# B133C.net
KiCad netlist of a schematic drawn in EAGLE
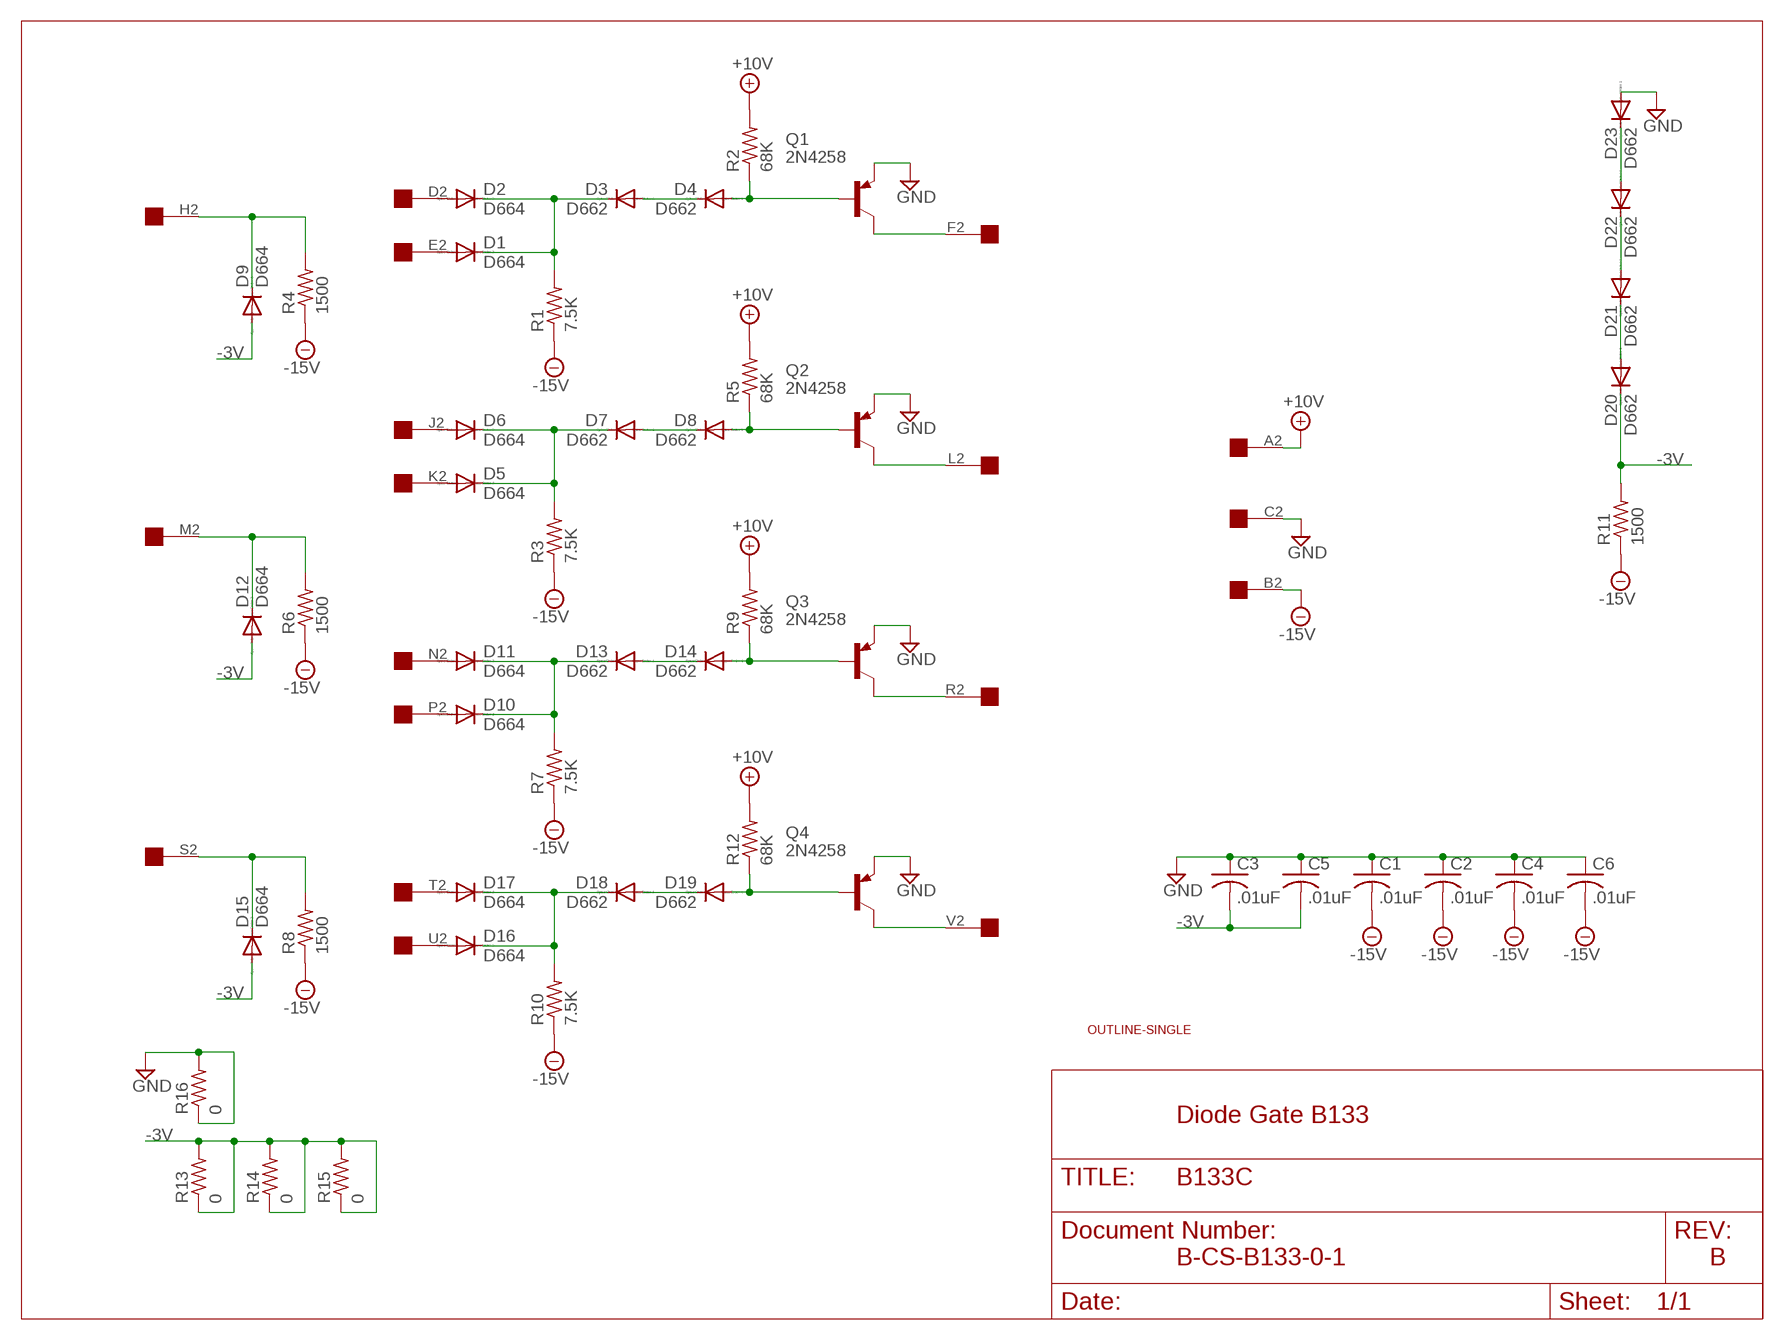
[diagram p0: schematic, sheet 1]

(export (version "E")
  (design (tool "Eeschema 10.0.6"))
  (components
    (comp (ref "C1")
      (value ".01uF")
      (footprint "eagle-import:C063-025X075")
      (libsource (lib "eagle-import") (part "C-US"))
    )
    (comp (ref "C2")
      (value ".01uF")
      (footprint "eagle-import:C063-025X075")
      (libsource (lib "eagle-import") (part "C-US"))
    )
    (comp (ref "C3")
      (value ".01uF")
      (footprint "eagle-import:C063-025X075")
      (libsource (lib "eagle-import") (part "C-US"))
    )
    (comp (ref "C4")
      (value ".01uF")
      (footprint "eagle-import:C063-025X075")
      (libsource (lib "eagle-import") (part "C-US"))
    )
    (comp (ref "C5")
      (value ".01uF")
      (footprint "eagle-import:C063-025X075")
      (libsource (lib "eagle-import") (part "C-US"))
    )
    (comp (ref "C6")
      (value ".01uF")
      (footprint "eagle-import:C063-025X075")
      (libsource (lib "eagle-import") (part "C-US"))
    )
    (comp (ref "D1")
      (value "D664")
      (footprint "eagle-import:DO35-10")
      (libsource (lib "eagle-import") (part "DIODE-DO35-10"))
    )
    (comp (ref "D2")
      (value "D664")
      (footprint "eagle-import:DO35-10")
      (libsource (lib "eagle-import") (part "DIODE-DO35-10"))
    )
    (comp (ref "D3")
      (value "D662")
      (footprint "eagle-import:DO35-10")
      (libsource (lib "eagle-import") (part "DIODE-DO35-10"))
    )
    (comp (ref "D4")
      (value "D662")
      (footprint "eagle-import:DO35-10")
      (libsource (lib "eagle-import") (part "DIODE-DO35-10"))
    )
    (comp (ref "D5")
      (value "D664")
      (footprint "eagle-import:DO35-10")
      (libsource (lib "eagle-import") (part "DIODE-DO35-10"))
    )
    (comp (ref "D6")
      (value "D664")
      (footprint "eagle-import:DO35-10")
      (libsource (lib "eagle-import") (part "DIODE-DO35-10"))
    )
    (comp (ref "D7")
      (value "D662")
      (footprint "eagle-import:DO35-10")
      (libsource (lib "eagle-import") (part "DIODE-DO35-10"))
    )
    (comp (ref "D8")
      (value "D662")
      (footprint "eagle-import:DO35-10")
      (libsource (lib "eagle-import") (part "DIODE-DO35-10"))
    )
    (comp (ref "D9")
      (value "D664")
      (footprint "eagle-import:DO35-10")
      (libsource (lib "eagle-import") (part "DIODE-DO35-10"))
    )
    (comp (ref "D10")
      (value "D664")
      (footprint "eagle-import:DO35-10")
      (libsource (lib "eagle-import") (part "DIODE-DO35-10"))
    )
    (comp (ref "D11")
      (value "D664")
      (footprint "eagle-import:DO35-10")
      (libsource (lib "eagle-import") (part "DIODE-DO35-10"))
    )
    (comp (ref "D12")
      (value "D664")
      (footprint "eagle-import:DO35-10")
      (libsource (lib "eagle-import") (part "DIODE-DO35-10"))
    )
    (comp (ref "D13")
      (value "D662")
      (footprint "eagle-import:DO35-10")
      (libsource (lib "eagle-import") (part "DIODE-DO35-10"))
    )
    (comp (ref "D14")
      (value "D662")
      (footprint "eagle-import:DO35-10")
      (libsource (lib "eagle-import") (part "DIODE-DO35-10"))
    )
    (comp (ref "D15")
      (value "D664")
      (footprint "eagle-import:DO35-10")
      (libsource (lib "eagle-import") (part "DIODE-DO35-10"))
    )
    (comp (ref "D16")
      (value "D664")
      (footprint "eagle-import:DO35-10")
      (libsource (lib "eagle-import") (part "DIODE-DO35-10"))
    )
    (comp (ref "D17")
      (value "D664")
      (footprint "eagle-import:DO35-10")
      (libsource (lib "eagle-import") (part "DIODE-DO35-10"))
    )
    (comp (ref "D18")
      (value "D662")
      (footprint "eagle-import:DO35-10")
      (libsource (lib "eagle-import") (part "DIODE-DO35-10"))
    )
    (comp (ref "D19")
      (value "D662")
      (footprint "eagle-import:DO35-10")
      (libsource (lib "eagle-import") (part "DIODE-DO35-10"))
    )
    (comp (ref "D20")
      (value "D662")
      (footprint "eagle-import:DO35-10")
      (libsource (lib "eagle-import") (part "DIODE-DO35-10"))
    )
    (comp (ref "D21")
      (value "D662")
      (footprint "eagle-import:DO35-10")
      (libsource (lib "eagle-import") (part "DIODE-DO35-10"))
    )
    (comp (ref "D22")
      (value "D662")
      (footprint "eagle-import:DO35-10")
      (libsource (lib "eagle-import") (part "DIODE-DO35-10"))
    )
    (comp (ref "D23")
      (value "D662")
      (footprint "eagle-import:DO35-10")
      (libsource (lib "eagle-import") (part "DIODE-DO35-10"))
    )
    (comp (ref "Q1")
      (value "2N4258")
      (footprint "eagle-import:TO5")
      (libsource (lib "eagle-import") (part "-PNP-TO5"))
    )
    (comp (ref "Q2")
      (value "2N4258")
      (footprint "eagle-import:TO5")
      (libsource (lib "eagle-import") (part "-PNP-TO5"))
    )
    (comp (ref "Q3")
      (value "2N4258")
      (footprint "eagle-import:TO5")
      (libsource (lib "eagle-import") (part "-PNP-TO5"))
    )
    (comp (ref "Q4")
      (value "2N4258")
      (footprint "eagle-import:TO5")
      (libsource (lib "eagle-import") (part "-PNP-TO5"))
    )
    (comp (ref "R1")
      (value "7.5K")
      (footprint "eagle-import:0207_10")
      (libsource (lib "eagle-import") (part "R-US_0207/10"))
    )
    (comp (ref "R2")
      (value "68K")
      (footprint "eagle-import:0207_10")
      (libsource (lib "eagle-import") (part "R-US_0207/10"))
    )
    (comp (ref "R3")
      (value "7.5K")
      (footprint "eagle-import:0207_10")
      (libsource (lib "eagle-import") (part "R-US_0207/10"))
    )
    (comp (ref "R4")
      (value "1500")
      (footprint "eagle-import:0207_10")
      (libsource (lib "eagle-import") (part "R-US_0207/10"))
    )
    (comp (ref "R5")
      (value "68K")
      (footprint "eagle-import:0207_10")
      (libsource (lib "eagle-import") (part "R-US_0207/10"))
    )
    (comp (ref "R6")
      (value "1500")
      (footprint "eagle-import:0207_10")
      (libsource (lib "eagle-import") (part "R-US_0207/10"))
    )
    (comp (ref "R7")
      (value "7.5K")
      (footprint "eagle-import:0207_10")
      (libsource (lib "eagle-import") (part "R-US_0207/10"))
    )
    (comp (ref "R8")
      (value "1500")
      (footprint "eagle-import:0207_10")
      (libsource (lib "eagle-import") (part "R-US_0207/10"))
    )
    (comp (ref "R9")
      (value "68K")
      (footprint "eagle-import:0207_10")
      (libsource (lib "eagle-import") (part "R-US_0207/10"))
    )
    (comp (ref "R10")
      (value "7.5K")
      (footprint "eagle-import:0207_10")
      (libsource (lib "eagle-import") (part "R-US_0207/10"))
    )
    (comp (ref "R11")
      (value "1500")
      (footprint "eagle-import:0207_10")
      (libsource (lib "eagle-import") (part "R-US_0207/10"))
    )
    (comp (ref "R12")
      (value "68K")
      (footprint "eagle-import:0207_10")
      (libsource (lib "eagle-import") (part "R-US_0207/10"))
    )
    (comp (ref "R13")
      (value "0")
      (footprint "eagle-import:0207_10")
      (libsource (lib "eagle-import") (part "R-US_0207/10"))
    )
    (comp (ref "R14")
      (value "0")
      (footprint "eagle-import:0207_10")
      (libsource (lib "eagle-import") (part "R-US_0207/10"))
    )
    (comp (ref "R15")
      (value "0")
      (footprint "eagle-import:0207_10")
      (libsource (lib "eagle-import") (part "R-US_0207/10"))
    )
    (comp (ref "R16")
      (value "0")
      (footprint "eagle-import:0207_10")
      (libsource (lib "eagle-import") (part "R-US_0207/10"))
    )
    (comp (ref "U$1")
      (value "OUTLINE-SINGLE")
      (footprint "eagle-import:SINGLE")
      (libsource (lib "eagle-import") (part "OUTLINE-SINGLE"))
    )
    (comp (ref "U$2")
      (value "EDGE-1")
      (footprint "eagle-import:EDGE-CON1")
      (libsource (lib "eagle-import") (part "EDGE-1"))
    )
  )
  (nets
    (net (code "1") (name "+10V") (class "Default")
      (node (ref "R12") (pin "2") (pinfunction "2_2") (pintype "passive"))
      (node (ref "R2") (pin "2") (pinfunction "2_2") (pintype "passive"))
      (node (ref "R5") (pin "2") (pinfunction "2_2") (pintype "passive"))
      (node (ref "R9") (pin "2") (pinfunction "2_2") (pintype "passive"))
      (node (ref "U$2") (pin "A2") (pinfunction "1_A2") (pintype "bidirectional"))
    )
    (net (code "2") (name "-15V") (class "Default")
      (node (ref "C1") (pin "2") (pinfunction "2_2") (pintype "passive"))
      (node (ref "C2") (pin "2") (pinfunction "2_2") (pintype "passive"))
      (node (ref "C4") (pin "2") (pinfunction "2_2") (pintype "passive"))
      (node (ref "C6") (pin "2") (pinfunction "2_2") (pintype "passive"))
      (node (ref "R1") (pin "1") (pinfunction "1_1") (pintype "passive"))
      (node (ref "R10") (pin "1") (pinfunction "1_1") (pintype "passive"))
      (node (ref "R11") (pin "1") (pinfunction "1_1") (pintype "passive"))
      (node (ref "R3") (pin "1") (pinfunction "1_1") (pintype "passive"))
      (node (ref "R4") (pin "1") (pinfunction "1_1") (pintype "passive"))
      (node (ref "R6") (pin "1") (pinfunction "1_1") (pintype "passive"))
      (node (ref "R7") (pin "1") (pinfunction "1_1") (pintype "passive"))
      (node (ref "R8") (pin "1") (pinfunction "1_1") (pintype "passive"))
      (node (ref "U$2") (pin "B2") (pinfunction "1_B2") (pintype "bidirectional"))
    )
    (net (code "3") (name "/-3V") (class "Default")
      (node (ref "C3") (pin "2") (pinfunction "2_2") (pintype "passive"))
      (node (ref "C5") (pin "2") (pinfunction "2_2") (pintype "passive"))
      (node (ref "D12") (pin "A") (pinfunction "A_A") (pintype "passive"))
      (node (ref "D15") (pin "A") (pinfunction "A_A") (pintype "passive"))
      (node (ref "D20") (pin "C") (pinfunction "C_C") (pintype "passive"))
      (node (ref "D9") (pin "A") (pinfunction "A_A") (pintype "passive"))
      (node (ref "R11") (pin "2") (pinfunction "2_2") (pintype "passive"))
      (node (ref "R13") (pin "1") (pinfunction "1_1") (pintype "passive"))
      (node (ref "R13") (pin "2") (pinfunction "2_2") (pintype "passive"))
      (node (ref "R14") (pin "1") (pinfunction "1_1") (pintype "passive"))
      (node (ref "R14") (pin "2") (pinfunction "2_2") (pintype "passive"))
      (node (ref "R15") (pin "1") (pinfunction "1_1") (pintype "passive"))
      (node (ref "R15") (pin "2") (pinfunction "2_2") (pintype "passive"))
    )
    (net (code "4") (name "GND") (class "Default")
      (node (ref "C1") (pin "1") (pinfunction "1_1") (pintype "passive"))
      (node (ref "C2") (pin "1") (pinfunction "1_1") (pintype "passive"))
      (node (ref "C3") (pin "1") (pinfunction "1_1") (pintype "passive"))
      (node (ref "C4") (pin "1") (pinfunction "1_1") (pintype "passive"))
      (node (ref "C5") (pin "1") (pinfunction "1_1") (pintype "passive"))
      (node (ref "C6") (pin "1") (pinfunction "1_1") (pintype "passive"))
      (node (ref "D23") (pin "A") (pinfunction "A_A") (pintype "passive"))
      (node (ref "Q1") (pin "1") (pinfunction "E_1") (pintype "passive"))
      (node (ref "Q2") (pin "1") (pinfunction "E_1") (pintype "passive"))
      (node (ref "Q3") (pin "1") (pinfunction "E_1") (pintype "passive"))
      (node (ref "Q4") (pin "1") (pinfunction "E_1") (pintype "passive"))
      (node (ref "R16") (pin "1") (pinfunction "1_1") (pintype "passive"))
      (node (ref "R16") (pin "2") (pinfunction "2_2") (pintype "passive"))
      (node (ref "U$2") (pin "C2") (pinfunction "1_C2") (pintype "bidirectional"))
    )
    (net (code "5") (name "Net-(D1-PadC)") (class "Default")
      (node (ref "D1") (pin "C") (pinfunction "C_C") (pintype "passive"))
      (node (ref "D2") (pin "C") (pinfunction "C_C") (pintype "passive"))
      (node (ref "D3") (pin "C") (pinfunction "C_C") (pintype "passive"))
      (node (ref "R1") (pin "2") (pinfunction "2_2") (pintype "passive"))
    )
    (net (code "6") (name "Net-(D3-PadA)") (class "Default")
      (node (ref "D3") (pin "A") (pinfunction "A_A") (pintype "passive"))
      (node (ref "D4") (pin "C") (pinfunction "C_C") (pintype "passive"))
    )
    (net (code "7") (name "Net-(D5-PadC)") (class "Default")
      (node (ref "D5") (pin "C") (pinfunction "C_C") (pintype "passive"))
      (node (ref "D6") (pin "C") (pinfunction "C_C") (pintype "passive"))
      (node (ref "D7") (pin "C") (pinfunction "C_C") (pintype "passive"))
      (node (ref "R3") (pin "2") (pinfunction "2_2") (pintype "passive"))
    )
    (net (code "8") (name "Net-(D7-PadA)") (class "Default")
      (node (ref "D7") (pin "A") (pinfunction "A_A") (pintype "passive"))
      (node (ref "D8") (pin "C") (pinfunction "C_C") (pintype "passive"))
    )
    (net (code "9") (name "Net-(D10-PadC)") (class "Default")
      (node (ref "D10") (pin "C") (pinfunction "C_C") (pintype "passive"))
      (node (ref "D11") (pin "C") (pinfunction "C_C") (pintype "passive"))
      (node (ref "D13") (pin "C") (pinfunction "C_C") (pintype "passive"))
      (node (ref "R7") (pin "2") (pinfunction "2_2") (pintype "passive"))
    )
    (net (code "10") (name "Net-(D13-PadA)") (class "Default")
      (node (ref "D13") (pin "A") (pinfunction "A_A") (pintype "passive"))
      (node (ref "D14") (pin "C") (pinfunction "C_C") (pintype "passive"))
    )
    (net (code "11") (name "Net-(D16-PadC)") (class "Default")
      (node (ref "D16") (pin "C") (pinfunction "C_C") (pintype "passive"))
      (node (ref "D17") (pin "C") (pinfunction "C_C") (pintype "passive"))
      (node (ref "D18") (pin "C") (pinfunction "C_C") (pintype "passive"))
      (node (ref "R10") (pin "2") (pinfunction "2_2") (pintype "passive"))
    )
    (net (code "12") (name "Net-(D18-PadA)") (class "Default")
      (node (ref "D18") (pin "A") (pinfunction "A_A") (pintype "passive"))
      (node (ref "D19") (pin "C") (pinfunction "C_C") (pintype "passive"))
    )
    (net (code "13") (name "Net-(D20-PadA)") (class "Default")
      (node (ref "D20") (pin "A") (pinfunction "A_A") (pintype "passive"))
      (node (ref "D21") (pin "C") (pinfunction "C_C") (pintype "passive"))
    )
    (net (code "14") (name "Net-(D21-PadA)") (class "Default")
      (node (ref "D21") (pin "A") (pinfunction "A_A") (pintype "passive"))
      (node (ref "D22") (pin "C") (pinfunction "C_C") (pintype "passive"))
    )
    (net (code "15") (name "Net-(D22-PadA)") (class "Default")
      (node (ref "D22") (pin "A") (pinfunction "A_A") (pintype "passive"))
      (node (ref "D23") (pin "C") (pinfunction "C_C") (pintype "passive"))
    )
    (net (code "16") (name "Net-(Q1-B)") (class "Default")
      (node (ref "D4") (pin "A") (pinfunction "A_A") (pintype "passive"))
      (node (ref "Q1") (pin "2") (pinfunction "B_2") (pintype "passive"))
      (node (ref "R2") (pin "1") (pinfunction "1_1") (pintype "passive"))
    )
    (net (code "17") (name "Net-(Q1-C)") (class "Default")
      (node (ref "Q1") (pin "3") (pinfunction "C_3") (pintype "passive"))
      (node (ref "U$2") (pin "F2") (pinfunction "1_F2") (pintype "bidirectional"))
    )
    (net (code "18") (name "Net-(Q2-B)") (class "Default")
      (node (ref "D8") (pin "A") (pinfunction "A_A") (pintype "passive"))
      (node (ref "Q2") (pin "2") (pinfunction "B_2") (pintype "passive"))
      (node (ref "R5") (pin "1") (pinfunction "1_1") (pintype "passive"))
    )
    (net (code "19") (name "Net-(Q2-C)") (class "Default")
      (node (ref "Q2") (pin "3") (pinfunction "C_3") (pintype "passive"))
      (node (ref "U$2") (pin "L2") (pinfunction "1_L2") (pintype "bidirectional"))
    )
    (net (code "20") (name "Net-(Q3-B)") (class "Default")
      (node (ref "D14") (pin "A") (pinfunction "A_A") (pintype "passive"))
      (node (ref "Q3") (pin "2") (pinfunction "B_2") (pintype "passive"))
      (node (ref "R9") (pin "1") (pinfunction "1_1") (pintype "passive"))
    )
    (net (code "21") (name "Net-(Q3-C)") (class "Default")
      (node (ref "Q3") (pin "3") (pinfunction "C_3") (pintype "passive"))
      (node (ref "U$2") (pin "R2") (pinfunction "1_R2") (pintype "bidirectional"))
    )
    (net (code "22") (name "Net-(Q4-B)") (class "Default")
      (node (ref "D19") (pin "A") (pinfunction "A_A") (pintype "passive"))
      (node (ref "Q4") (pin "2") (pinfunction "B_2") (pintype "passive"))
      (node (ref "R12") (pin "1") (pinfunction "1_1") (pintype "passive"))
    )
    (net (code "23") (name "Net-(Q4-C)") (class "Default")
      (node (ref "Q4") (pin "3") (pinfunction "C_3") (pintype "passive"))
      (node (ref "U$2") (pin "V2") (pinfunction "1_V2") (pintype "bidirectional"))
    )
    (net (code "24") (name "Net-(U$2D-1)") (class "Default")
      (node (ref "D2") (pin "A") (pinfunction "A_A") (pintype "passive"))
      (node (ref "U$2") (pin "D2") (pinfunction "1_D2") (pintype "bidirectional"))
    )
    (net (code "25") (name "Net-(U$2E-1)") (class "Default")
      (node (ref "D1") (pin "A") (pinfunction "A_A") (pintype "passive"))
      (node (ref "U$2") (pin "E2") (pinfunction "1_E2") (pintype "bidirectional"))
    )
    (net (code "26") (name "Net-(U$2G-1)") (class "Default")
      (node (ref "D9") (pin "C") (pinfunction "C_C") (pintype "passive"))
      (node (ref "R4") (pin "2") (pinfunction "2_2") (pintype "passive"))
      (node (ref "U$2") (pin "H2") (pinfunction "1_H2") (pintype "bidirectional"))
    )
    (net (code "27") (name "Net-(U$2H-1)") (class "Default")
      (node (ref "D6") (pin "A") (pinfunction "A_A") (pintype "passive"))
      (node (ref "U$2") (pin "J2") (pinfunction "1_J2") (pintype "bidirectional"))
    )
    (net (code "28") (name "Net-(U$2I-1)") (class "Default")
      (node (ref "D5") (pin "A") (pinfunction "A_A") (pintype "passive"))
      (node (ref "U$2") (pin "K2") (pinfunction "1_K2") (pintype "bidirectional"))
    )
    (net (code "29") (name "Net-(U$2K-1)") (class "Default")
      (node (ref "D12") (pin "C") (pinfunction "C_C") (pintype "passive"))
      (node (ref "R6") (pin "2") (pinfunction "2_2") (pintype "passive"))
      (node (ref "U$2") (pin "M2") (pinfunction "1_M2") (pintype "bidirectional"))
    )
    (net (code "30") (name "Net-(U$2L-1)") (class "Default")
      (node (ref "D11") (pin "A") (pinfunction "A_A") (pintype "passive"))
      (node (ref "U$2") (pin "N2") (pinfunction "1_N2") (pintype "bidirectional"))
    )
    (net (code "31") (name "Net-(U$2M-1)") (class "Default")
      (node (ref "D10") (pin "A") (pinfunction "A_A") (pintype "passive"))
      (node (ref "U$2") (pin "P2") (pinfunction "1_P2") (pintype "bidirectional"))
    )
    (net (code "32") (name "Net-(U$2O-1)") (class "Default")
      (node (ref "D15") (pin "C") (pinfunction "C_C") (pintype "passive"))
      (node (ref "R8") (pin "2") (pinfunction "2_2") (pintype "passive"))
      (node (ref "U$2") (pin "S2") (pinfunction "1_S2") (pintype "bidirectional"))
    )
    (net (code "33") (name "Net-(U$2P-1)") (class "Default")
      (node (ref "D17") (pin "A") (pinfunction "A_A") (pintype "passive"))
      (node (ref "U$2") (pin "T2") (pinfunction "1_T2") (pintype "bidirectional"))
    )
    (net (code "34") (name "Net-(U$2Q-1)") (class "Default")
      (node (ref "D16") (pin "A") (pinfunction "A_A") (pintype "passive"))
      (node (ref "U$2") (pin "U2") (pinfunction "1_U2") (pintype "bidirectional"))
    )
  )
)
